# AUX_SteeringWheel_v4.net
KiCad netlist of a schematic drawn in Altium Designer
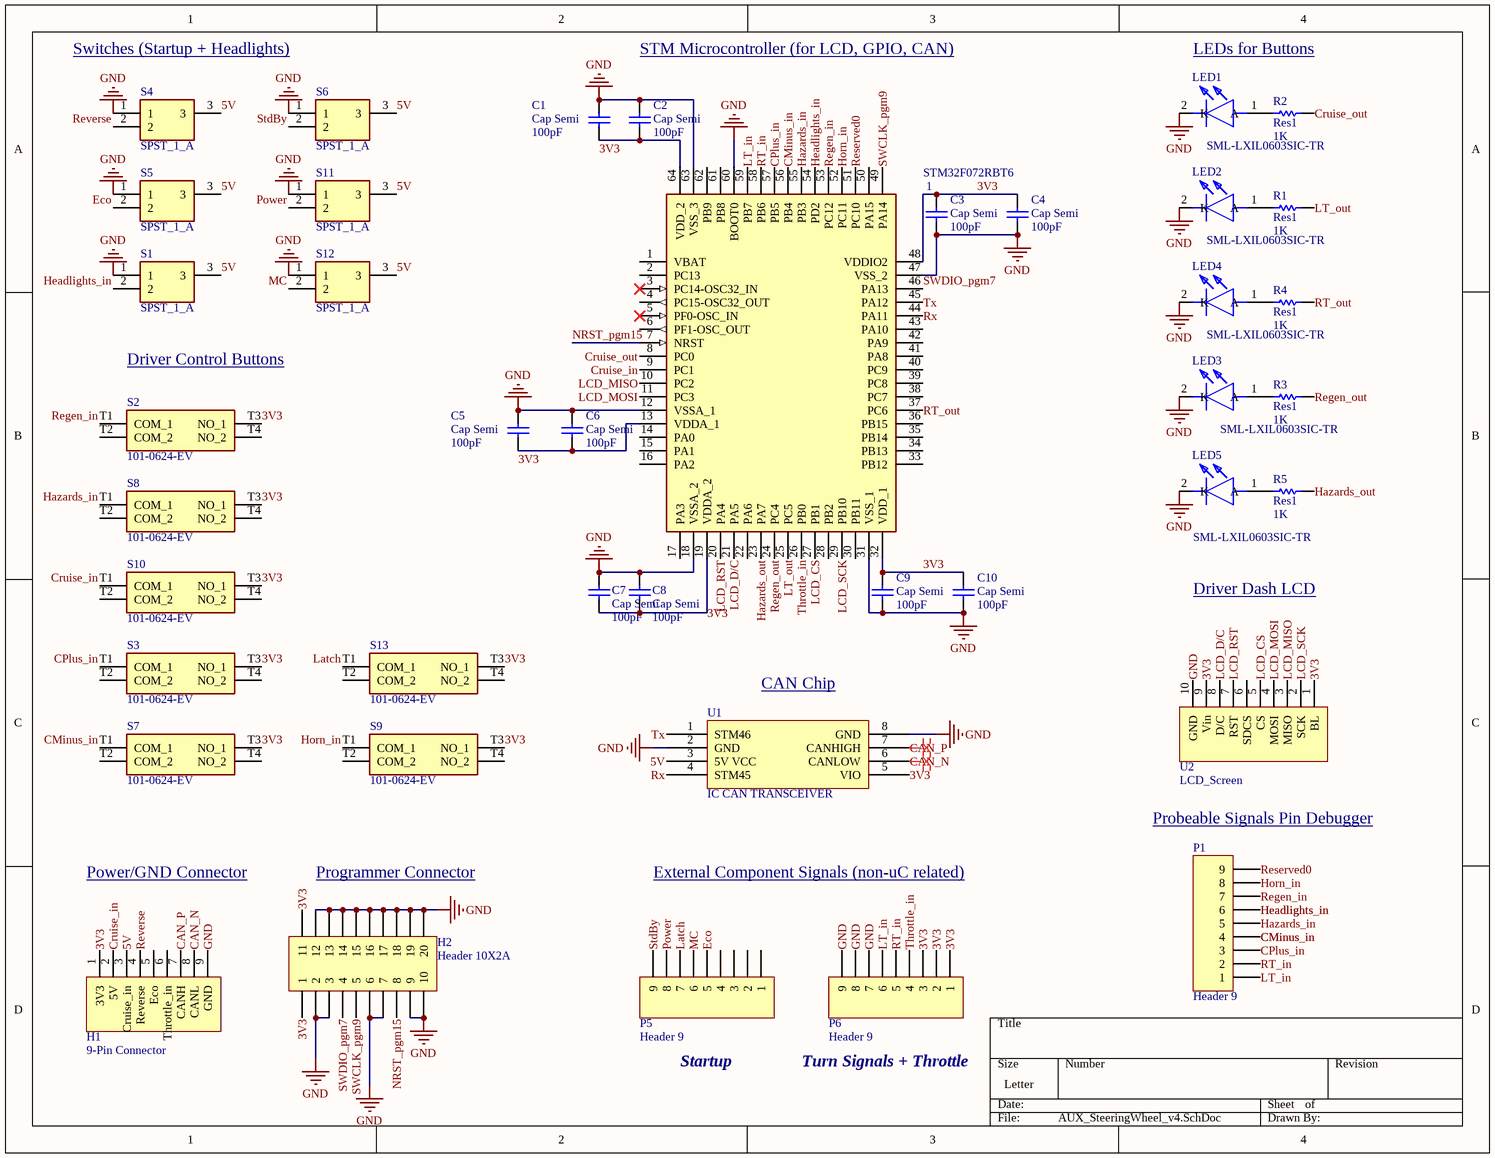
[diagram p0: AUX_SteeringWheel_v4.SchDoc]

(export (version "E")
  (design (tool "Eeschema 10.0.6"))
  (components
    (comp (ref "1")
      (value "STM32F072RBT6")
      (footprint "QFP50P1200X1200X160-64N")
      (description "Integrated Circuit")
      (fields (field (name "MOUSER PART NUMBER") "511-STM32F072RBT6"))
      (libsource (lib "AUX_SteeringWheel_v3") (part "STM32F072RBT6"))
    )
    (comp (ref "C1")
      (value "Cap Semi")
      (footprint "C1206")
      (description "Capacitor (Semiconductor SIM Model)")
      (fields (field (name "ALTIUM_VALUE") "100pF") (field (name "PUBLISHER") "Altium Limited"))
      (libsource (lib "Miscellaneous Devices") (part "Cap Semi"))
    )
    (comp (ref "C2")
      (value "Cap Semi")
      (footprint "C1206")
      (description "Capacitor (Semiconductor SIM Model)")
      (fields (field (name "ALTIUM_VALUE") "100pF") (field (name "PUBLISHER") "Altium Limited"))
      (libsource (lib "Miscellaneous Devices") (part "Cap Semi"))
    )
    (comp (ref "C3")
      (value "Cap Semi")
      (footprint "C1206")
      (description "Capacitor (Semiconductor SIM Model)")
      (fields (field (name "ALTIUM_VALUE") "100pF") (field (name "PUBLISHER") "Altium Limited"))
      (libsource (lib "Miscellaneous Devices") (part "Cap Semi"))
    )
    (comp (ref "C4")
      (value "Cap Semi")
      (footprint "C1206")
      (description "Capacitor (Semiconductor SIM Model)")
      (fields (field (name "ALTIUM_VALUE") "100pF") (field (name "PUBLISHER") "Altium Limited"))
      (libsource (lib "Miscellaneous Devices") (part "Cap Semi"))
    )
    (comp (ref "C5")
      (value "Cap Semi")
      (footprint "C1206")
      (description "Capacitor (Semiconductor SIM Model)")
      (fields (field (name "ALTIUM_VALUE") "100pF") (field (name "PUBLISHER") "Altium Limited"))
      (libsource (lib "Miscellaneous Devices") (part "Cap Semi"))
    )
    (comp (ref "C6")
      (value "Cap Semi")
      (footprint "C1206")
      (description "Capacitor (Semiconductor SIM Model)")
      (fields (field (name "ALTIUM_VALUE") "100pF") (field (name "PUBLISHER") "Altium Limited"))
      (libsource (lib "Miscellaneous Devices") (part "Cap Semi"))
    )
    (comp (ref "C7")
      (value "Cap Semi")
      (footprint "C1206")
      (description "Capacitor (Semiconductor SIM Model)")
      (fields (field (name "ALTIUM_VALUE") "100pF") (field (name "PUBLISHER") "Altium Limited"))
      (libsource (lib "Miscellaneous Devices") (part "Cap Semi"))
    )
    (comp (ref "C8")
      (value "Cap Semi")
      (footprint "C1206")
      (description "Capacitor (Semiconductor SIM Model)")
      (fields (field (name "ALTIUM_VALUE") "100pF") (field (name "PUBLISHER") "Altium Limited"))
      (libsource (lib "Miscellaneous Devices") (part "Cap Semi"))
    )
    (comp (ref "C9")
      (value "Cap Semi")
      (footprint "C1206")
      (description "Capacitor (Semiconductor SIM Model)")
      (fields (field (name "ALTIUM_VALUE") "100pF") (field (name "PUBLISHER") "Altium Limited"))
      (libsource (lib "Miscellaneous Devices") (part "Cap Semi"))
    )
    (comp (ref "C10")
      (value "Cap Semi")
      (footprint "C1206")
      (description "Capacitor (Semiconductor SIM Model)")
      (fields (field (name "ALTIUM_VALUE") "100pF") (field (name "PUBLISHER") "Altium Limited"))
      (libsource (lib "Miscellaneous Devices") (part "Cap Semi"))
    )
    (comp (ref "H1")
      (value "9-Pin Connector")
      (footprint "Rt_Angle_9-Pin")
      (libsource (lib "Aux_Lights_Daughter_library") (part "9-Pin Connector"))
    )
    (comp (ref "H2")
      (value "Header 10X2A")
      (footprint "HDR2X10_CEN")
      (description "Header, 10-Pin, Dual row")
      (fields (field (name "PUBLISHER") "Altium Limited"))
      (libsource (lib "Miscellaneous Connectors") (part "Header 10X2A"))
    )
    (comp (ref "LED1")
      (value "SML-LXIL0603SIC-TR")
      (footprint "LED thru hole")
      (description "Cruise")
      (fields (field (name "MOUSER2 PART NUMBER") "696-SMLLXIL0603SICTR"))
      (libsource (lib "*") (part "SML-LXIL0603SIC-TR"))
    )
    (comp (ref "LED2")
      (value "SML-LXIL0603SIC-TR")
      (footprint "LED thru hole")
      (description "Cruise")
      (fields (field (name "MOUSER2 PART NUMBER") "696-SMLLXIL0603SICTR"))
      (libsource (lib "*") (part "SML-LXIL0603SIC-TR"))
    )
    (comp (ref "LED3")
      (value "SML-LXIL0603SIC-TR")
      (footprint "LED thru hole")
      (description "Headlights")
      (fields (field (name "MOUSER2 PART NUMBER") "696-SMLLXIL0603SICTR"))
      (libsource (lib "*") (part "SML-LXIL0603SIC-TR"))
    )
    (comp (ref "LED4")
      (value "SML-LXIL0603SIC-TR")
      (footprint "LED thru hole")
      (description "Cruise")
      (fields (field (name "MOUSER2 PART NUMBER") "696-SMLLXIL0603SICTR"))
      (libsource (lib "*") (part "SML-LXIL0603SIC-TR"))
    )
    (comp (ref "LED5")
      (value "SML-LXIL0603SIC-TR")
      (footprint "LED thru hole")
      (description "Hazards")
      (fields (field (name "MOUSER2 PART NUMBER") "696-SMLLXIL0603SICTR"))
      (libsource (lib "*") (part "SML-LXIL0603SIC-TR"))
    )
    (comp (ref "P1")
      (value "Header 9")
      (footprint "HDR1X9")
      (description "Header, 9-Pin")
      (fields (field (name "PUBLISHER") "Altium Limited"))
      (libsource (lib "") (part "Header 9_1"))
    )
    (comp (ref "P5")
      (value "Header 9")
      (footprint "Rt_Angle_9-Pin")
      (description "Header, 9-Pin")
      (fields (field (name "PUBLISHER") "Altium Limited"))
      (libsource (lib "Miscellaneous Connectors") (part "Header 9"))
    )
    (comp (ref "P6")
      (value "Header 9")
      (footprint "Rt_Angle_9-Pin")
      (description "Header, 9-Pin")
      (fields (field (name "PUBLISHER") "Altium Limited"))
      (libsource (lib "Miscellaneous Connectors") (part "Header 9"))
    )
    (comp (ref "R1")
      (value "Res1")
      (footprint "AXIAL-0.3")
      (description "Resistor")
      (fields (field (name "ALTIUM_VALUE") "1K") (field (name "PUBLISHER") "Altium Limited"))
      (libsource (lib "Miscellaneous Devices") (part "Res1"))
    )
    (comp (ref "R2")
      (value "Res1")
      (footprint "AXIAL-0.3")
      (description "Resistor")
      (fields (field (name "ALTIUM_VALUE") "1K") (field (name "PUBLISHER") "Altium Limited"))
      (libsource (lib "Miscellaneous Devices") (part "Res1"))
    )
    (comp (ref "R3")
      (value "Res1")
      (footprint "AXIAL-0.3")
      (description "Resistor")
      (fields (field (name "ALTIUM_VALUE") "1K") (field (name "PUBLISHER") "Altium Limited"))
      (libsource (lib "Miscellaneous Devices") (part "Res1"))
    )
    (comp (ref "R4")
      (value "Res1")
      (footprint "AXIAL-0.3")
      (description "Resistor")
      (fields (field (name "ALTIUM_VALUE") "1K") (field (name "PUBLISHER") "Altium Limited"))
      (libsource (lib "Miscellaneous Devices") (part "Res1"))
    )
    (comp (ref "R5")
      (value "Res1")
      (footprint "AXIAL-0.3")
      (description "Resistor")
      (fields (field (name "ALTIUM_VALUE") "1K") (field (name "PUBLISHER") "Altium Limited"))
      (libsource (lib "Miscellaneous Devices") (part "Res1"))
    )
    (comp (ref "S1")
      (value "SPST_1_A")
      (footprint "2M1SP3T1B1M2QE")
      (description "Switch")
      (fields
        (field (name "MOUSER PART NUMBER") "691-2M1-SP1-T1B1M2QE")
        (field (name "MANUFACTURER_PART_NUMBER") "2M1-SP1-T1-B1-M2QE")
      )
      (libsource (lib "AUX_v7_3") (part "2M1-SP1-T1-B1-M2QE"))
    )
    (comp (ref "S2")
      (value "101-0624-EV")
      (footprint "1010624EV")
      (description "Switch")
      (libsource (lib "AUX_SteeringWheel_v3") (part "101-0624-EV"))
    )
    (comp (ref "S3")
      (value "101-0624-EV")
      (footprint "1010624EV")
      (description "Switch")
      (libsource (lib "AUX_SteeringWheel_v3") (part "101-0624-EV"))
    )
    (comp (ref "S4")
      (value "SPST_1_A")
      (footprint "2M1SP3T1B1M2QE")
      (description "Switch")
      (fields
        (field (name "MOUSER PART NUMBER") "691-2M1-SP1-T1B1M2QE")
        (field (name "MANUFACTURER_PART_NUMBER") "2M1-SP1-T1-B1-M2QE")
      )
      (libsource (lib "AUX_SteeringWheel_v3") (part "2M1-SP1-T1-B1-M2QE"))
    )
    (comp (ref "S5")
      (value "SPST_1_A")
      (footprint "2M1SP3T1B1M2QE")
      (description "Switch")
      (fields
        (field (name "MOUSER PART NUMBER") "691-2M1-SP1-T1B1M2QE")
        (field (name "MANUFACTURER_PART_NUMBER") "2M1-SP1-T1-B1-M2QE")
      )
      (libsource (lib "AUX_SteeringWheel_v3") (part "2M1-SP1-T1-B1-M2QE"))
    )
    (comp (ref "S6")
      (value "SPST_1_A")
      (footprint "2M1SP3T1B1M2QE")
      (description "Switch")
      (fields
        (field (name "MOUSER PART NUMBER") "691-2M1-SP1-T1B1M2QE")
        (field (name "MANUFACTURER_PART_NUMBER") "2M1-SP1-T1-B1-M2QE")
      )
      (libsource (lib "AUX_SteeringWheel_v3") (part "2M1-SP1-T1-B1-M2QE"))
    )
    (comp (ref "S7")
      (value "101-0624-EV")
      (footprint "1010624EV")
      (description "Switch")
      (libsource (lib "AUX_SteeringWheel_v3") (part "101-0624-EV"))
    )
    (comp (ref "S8")
      (value "101-0624-EV")
      (footprint "1010624EV")
      (description "Switch")
      (libsource (lib "AUX_SteeringWheel_v3") (part "101-0624-EV"))
    )
    (comp (ref "S9")
      (value "101-0624-EV")
      (footprint "1010624EV")
      (description "Switch")
      (libsource (lib "AUX_SteeringWheel_v3") (part "101-0624-EV"))
    )
    (comp (ref "S10")
      (value "101-0624-EV")
      (footprint "1010624EV")
      (description "Switch")
      (libsource (lib "AUX_SteeringWheel_v3") (part "101-0624-EV"))
    )
    (comp (ref "S11")
      (value "SPST_1_A")
      (footprint "2M1SP3T1B1M2QE")
      (description "Switch")
      (fields
        (field (name "MOUSER PART NUMBER") "691-2M1-SP1-T1B1M2QE")
        (field (name "MANUFACTURER_PART_NUMBER") "2M1-SP1-T1-B1-M2QE")
      )
      (libsource (lib "AUX_SteeringWheel_v3") (part "2M1-SP1-T1-B1-M2QE"))
    )
    (comp (ref "S12")
      (value "SPST_1_A")
      (footprint "2M1SP3T1B1M2QE")
      (description "Switch")
      (fields
        (field (name "MOUSER PART NUMBER") "691-2M1-SP1-T1B1M2QE")
        (field (name "MANUFACTURER_PART_NUMBER") "2M1-SP1-T1-B1-M2QE")
      )
      (libsource (lib "AUX_SteeringWheel_v3") (part "2M1-SP1-T1-B1-M2QE"))
    )
    (comp (ref "S13")
      (value "101-0624-EV")
      (footprint "1010624EV")
      (description "Switch")
      (libsource (lib "AUX_SteeringWheel_v3") (part "101-0624-EV"))
    )
    (comp (ref "U1")
      (value "IC CAN TRANSCEIVER")
      (footprint "CAN TRANSCEIVER")
      (libsource (lib "Components") (part "CAN TRANSCEIVER"))
    )
    (comp (ref "U2")
      (value "LCD_Screen")
      (footprint "LCD_Screen")
      (description "LCD Display Screen")
      (libsource (lib "Aux_Lights_Daughter_library") (part "LCD_Screen"))
    )
  )
  (nets
    (net (code "1") (name "/3V3") (class "Default")
      (node (ref "1") (pin "13") (pinfunction "VDDA_1_13") (pintype "power_in"))
      (node (ref "1") (pin "19") (pinfunction "VDDA_2_19") (pintype "power_in"))
      (node (ref "1") (pin "32") (pinfunction "VDD_1_32") (pintype "power_in"))
      (node (ref "1") (pin "48") (pinfunction "VDDIO2_48") (pintype "power_in"))
      (node (ref "1") (pin "64") (pinfunction "VDD_2_64") (pintype "power_in"))
      (node (ref "C1") (pin "1") (pinfunction "1_1") (pintype "passive"))
      (node (ref "C10") (pin "2") (pinfunction "2_2") (pintype "passive"))
      (node (ref "C2") (pin "1") (pinfunction "1_1") (pintype "passive"))
      (node (ref "C3") (pin "2") (pinfunction "2_2") (pintype "passive"))
      (node (ref "C4") (pin "2") (pinfunction "2_2") (pintype "passive"))
      (node (ref "C5") (pin "1") (pinfunction "1_1") (pintype "passive"))
      (node (ref "C6") (pin "1") (pinfunction "1_1") (pintype "passive"))
      (node (ref "C7") (pin "1") (pinfunction "1_1") (pintype "passive"))
      (node (ref "C8") (pin "1") (pinfunction "1_1") (pintype "passive"))
      (node (ref "C9") (pin "2") (pinfunction "2_2") (pintype "passive"))
      (node (ref "H1") (pin "1") (pinfunction "3V3_1") (pintype "passive"))
      (node (ref "H2") (pin "1") (pinfunction "1_1") (pintype "passive"))
      (node (ref "H2") (pin "11") (pinfunction "11_11") (pintype "passive"))
      (node (ref "P6") (pin "1") (pinfunction "1_1") (pintype "passive"))
      (node (ref "P6") (pin "2") (pinfunction "2_2") (pintype "passive"))
      (node (ref "P6") (pin "3") (pinfunction "3_3") (pintype "passive"))
      (node (ref "S10") (pin "T3") (pinfunction "NO_1_T3") (pintype "passive"))
      (node (ref "S13") (pin "T3") (pinfunction "NO_1_T3") (pintype "passive"))
      (node (ref "S2") (pin "T3") (pinfunction "NO_1_T3") (pintype "passive"))
      (node (ref "S3") (pin "T3") (pinfunction "NO_1_T3") (pintype "passive"))
      (node (ref "S7") (pin "T3") (pinfunction "NO_1_T3") (pintype "passive"))
      (node (ref "S8") (pin "T3") (pinfunction "NO_1_T3") (pintype "passive"))
      (node (ref "S9") (pin "T3") (pinfunction "NO_1_T3") (pintype "passive"))
      (node (ref "U1") (pin "5") (pinfunction "VIO_5") (pintype "passive"))
      (node (ref "U2") (pin "1") (pinfunction "BL_1") (pintype "passive"))
      (node (ref "U2") (pin "9") (pinfunction "Vin_9") (pintype "passive"))
    )
    (net (code "2") (name "/5V") (class "Default")
      (node (ref "H1") (pin "3") (pinfunction "Cruise_in_3") (pintype "passive"))
      (node (ref "S1") (pin "3") (pinfunction "3_3") (pintype "passive"))
      (node (ref "S11") (pin "3") (pinfunction "3_3") (pintype "passive"))
      (node (ref "S12") (pin "3") (pinfunction "3_3") (pintype "passive"))
      (node (ref "S4") (pin "3") (pinfunction "3_3") (pintype "passive"))
      (node (ref "S5") (pin "3") (pinfunction "3_3") (pintype "passive"))
      (node (ref "S6") (pin "3") (pinfunction "3_3") (pintype "passive"))
      (node (ref "U1") (pin "3") (pinfunction "5V_VCC_3") (pintype "passive"))
    )
    (net (code "3") (name "/CAN_N") (class "Default")
      (node (ref "H1") (pin "8") (pinfunction "CANL_8") (pintype "passive"))
      (node (ref "U1") (pin "6") (pinfunction "CANLOW_6") (pintype "passive"))
    )
    (net (code "4") (name "/CAN_P") (class "Default")
      (node (ref "H1") (pin "7") (pinfunction "CANH_7") (pintype "passive"))
      (node (ref "U1") (pin "7") (pinfunction "CANHIGH_7") (pintype "passive"))
    )
    (net (code "5") (name "/CMinus_in") (class "Default")
      (node (ref "1") (pin "56") (pinfunction "PB4_56") (pintype "passive"))
      (node (ref "P1") (pin "4") (pinfunction "4_4") (pintype "passive"))
      (node (ref "S7") (pin "T1") (pinfunction "COM_1_T1") (pintype "passive"))
    )
    (net (code "6") (name "/CPlus_in") (class "Default")
      (node (ref "1") (pin "57") (pinfunction "PB5_57") (pintype "passive"))
      (node (ref "P1") (pin "3") (pinfunction "3_3") (pintype "passive"))
      (node (ref "S3") (pin "T1") (pinfunction "COM_1_T1") (pintype "passive"))
    )
    (net (code "7") (name "/Cruise_in") (class "Default")
      (node (ref "1") (pin "9") (pinfunction "PC1_9") (pintype "passive"))
      (node (ref "H1") (pin "2") (pinfunction "5V_2") (pintype "passive"))
      (node (ref "S10") (pin "T1") (pinfunction "COM_1_T1") (pintype "passive"))
    )
    (net (code "8") (name "/Cruise_out") (class "Default")
      (node (ref "1") (pin "8") (pinfunction "PC0_8") (pintype "passive"))
      (node (ref "R2") (pin "1") (pinfunction "1_1") (pintype "passive"))
    )
    (net (code "9") (name "/Eco") (class "Default")
      (node (ref "P5") (pin "5") (pinfunction "5_5") (pintype "passive"))
      (node (ref "S5") (pin "2") (pinfunction "2_2") (pintype "passive"))
    )
    (net (code "10") (name "/Hazards_in") (class "Default")
      (node (ref "1") (pin "55") (pinfunction "PB3_55") (pintype "passive"))
      (node (ref "P1") (pin "5") (pinfunction "5_5") (pintype "passive"))
      (node (ref "S8") (pin "T1") (pinfunction "COM_1_T1") (pintype "passive"))
    )
    (net (code "11") (name "/Hazards_out") (class "Default")
      (node (ref "1") (pin "23") (pinfunction "PA7_23") (pintype "passive"))
      (node (ref "R5") (pin "1") (pinfunction "1_1") (pintype "passive"))
    )
    (net (code "12") (name "/Headlights_in") (class "Default")
      (node (ref "1") (pin "54") (pinfunction "PD2_54") (pintype "passive"))
      (node (ref "P1") (pin "6") (pinfunction "6_6") (pintype "passive"))
      (node (ref "S1") (pin "2") (pinfunction "2_2") (pintype "passive"))
    )
    (net (code "13") (name "/Horn_in") (class "Default")
      (node (ref "1") (pin "52") (pinfunction "PC11_52") (pintype "passive"))
      (node (ref "P1") (pin "8") (pinfunction "8_8") (pintype "passive"))
      (node (ref "S9") (pin "T1") (pinfunction "COM_1_T1") (pintype "passive"))
    )
    (net (code "14") (name "/LCD_CS") (class "Default")
      (node (ref "1") (pin "27") (pinfunction "PB1_27") (pintype "passive"))
      (node (ref "U2") (pin "5") (pinfunction "CS_5") (pintype "passive"))
    )
    (net (code "15") (name "/LCD_D{slash}C") (class "Default")
      (node (ref "1") (pin "21") (pinfunction "PA5_21") (pintype "passive"))
      (node (ref "U2") (pin "8") (pinfunction "D/C_8") (pintype "passive"))
    )
    (net (code "16") (name "/LCD_MISO") (class "Default")
      (node (ref "1") (pin "10") (pinfunction "PC2_10") (pintype "passive"))
      (node (ref "U2") (pin "3") (pinfunction "MISO_3") (pintype "passive"))
    )
    (net (code "17") (name "/LCD_MOSI") (class "Default")
      (node (ref "1") (pin "11") (pinfunction "PC3_11") (pintype "passive"))
      (node (ref "U2") (pin "4") (pinfunction "MOSI_4") (pintype "passive"))
    )
    (net (code "18") (name "/LCD_RST") (class "Default")
      (node (ref "1") (pin "20") (pinfunction "PA4_20") (pintype "passive"))
      (node (ref "U2") (pin "7") (pinfunction "RST_7") (pintype "passive"))
    )
    (net (code "19") (name "/LCD_SCK") (class "Default")
      (node (ref "1") (pin "29") (pinfunction "PB10_29") (pintype "passive"))
      (node (ref "U2") (pin "2") (pinfunction "SCK_2") (pintype "passive"))
    )
    (net (code "20") (name "/LT_in") (class "Default")
      (node (ref "1") (pin "59") (pinfunction "PB7_59") (pintype "passive"))
      (node (ref "P1") (pin "1") (pinfunction "1_1") (pintype "passive"))
      (node (ref "P6") (pin "6") (pinfunction "6_6") (pintype "passive"))
    )
    (net (code "21") (name "/LT_out") (class "Default")
      (node (ref "1") (pin "25") (pinfunction "PC5_25") (pintype "passive"))
      (node (ref "R1") (pin "1") (pinfunction "1_1") (pintype "passive"))
    )
    (net (code "22") (name "/Latch") (class "Default")
      (node (ref "P5") (pin "7") (pinfunction "7_7") (pintype "passive"))
      (node (ref "S13") (pin "T1") (pinfunction "COM_1_T1") (pintype "passive"))
    )
    (net (code "23") (name "/MC") (class "Default")
      (node (ref "P5") (pin "6") (pinfunction "6_6") (pintype "passive"))
      (node (ref "S12") (pin "2") (pinfunction "2_2") (pintype "passive"))
    )
    (net (code "24") (name "/NRST_pgm15") (class "Default")
      (node (ref "1") (pin "7") (pinfunction "NRST_7") (pintype "input"))
      (node (ref "H2") (pin "8") (pinfunction "8_8") (pintype "passive"))
    )
    (net (code "25") (name "/Power") (class "Default")
      (node (ref "P5") (pin "8") (pinfunction "8_8") (pintype "passive"))
      (node (ref "S11") (pin "2") (pinfunction "2_2") (pintype "passive"))
    )
    (net (code "26") (name "/RT_in") (class "Default")
      (node (ref "1") (pin "58") (pinfunction "PB6_58") (pintype "passive"))
      (node (ref "P1") (pin "2") (pinfunction "2_2") (pintype "passive"))
      (node (ref "P6") (pin "5") (pinfunction "5_5") (pintype "passive"))
    )
    (net (code "27") (name "/RT_out") (class "Default")
      (node (ref "1") (pin "37") (pinfunction "PC6_37") (pintype "passive"))
      (node (ref "R4") (pin "1") (pinfunction "1_1") (pintype "passive"))
    )
    (net (code "28") (name "/Regen_in") (class "Default")
      (node (ref "1") (pin "53") (pinfunction "PC12_53") (pintype "passive"))
      (node (ref "P1") (pin "7") (pinfunction "7_7") (pintype "passive"))
      (node (ref "S2") (pin "T1") (pinfunction "COM_1_T1") (pintype "passive"))
    )
    (net (code "29") (name "/Regen_out") (class "Default")
      (node (ref "1") (pin "24") (pinfunction "PC4_24") (pintype "passive"))
      (node (ref "R3") (pin "1") (pinfunction "1_1") (pintype "passive"))
    )
    (net (code "30") (name "/Reserved0") (class "Default")
      (node (ref "1") (pin "51") (pinfunction "PC10_51") (pintype "passive"))
      (node (ref "P1") (pin "9") (pinfunction "9_9") (pintype "passive"))
    )
    (net (code "31") (name "/Reverse") (class "Default")
      (node (ref "H1") (pin "4") (pinfunction "Reverse_4") (pintype "passive"))
      (node (ref "S4") (pin "2") (pinfunction "2_2") (pintype "passive"))
    )
    (net (code "32") (name "/Rx") (class "Default")
      (node (ref "1") (pin "44") (pinfunction "PA11_44") (pintype "passive"))
      (node (ref "U1") (pin "4") (pinfunction "STM45_4") (pintype "passive"))
    )
    (net (code "33") (name "/SWCLK_pgm9") (class "Default")
      (node (ref "1") (pin "49") (pinfunction "PA14_49") (pintype "passive"))
      (node (ref "H2") (pin "5") (pinfunction "5_5") (pintype "passive"))
    )
    (net (code "34") (name "/SWDIO_pgm7") (class "Default")
      (node (ref "1") (pin "46") (pinfunction "PA13_46") (pintype "passive"))
      (node (ref "H2") (pin "4") (pinfunction "4_4") (pintype "passive"))
    )
    (net (code "35") (name "/StdBy") (class "Default")
      (node (ref "P5") (pin "9") (pinfunction "9_9") (pintype "passive"))
      (node (ref "S6") (pin "2") (pinfunction "2_2") (pintype "passive"))
    )
    (net (code "36") (name "/Throttle_in") (class "Default")
      (node (ref "1") (pin "26") (pinfunction "PB0_26") (pintype "passive"))
      (node (ref "P6") (pin "4") (pinfunction "4_4") (pintype "passive"))
    )
    (net (code "37") (name "/Tx") (class "Default")
      (node (ref "1") (pin "45") (pinfunction "PA12_45") (pintype "passive"))
      (node (ref "U1") (pin "1") (pinfunction "STM46_1") (pintype "passive"))
    )
    (net (code "38") (name "GND") (class "Default")
      (node (ref "1") (pin "12") (pinfunction "VSSA_1_12") (pintype "power_in"))
      (node (ref "1") (pin "18") (pinfunction "VSSA_2_18") (pintype "power_in"))
      (node (ref "1") (pin "31") (pinfunction "VSS_1_31") (pintype "power_in"))
      (node (ref "1") (pin "47") (pinfunction "VSS_2_47") (pintype "power_in"))
      (node (ref "1") (pin "60") (pinfunction "BOOT0_60") (pintype "passive"))
      (node (ref "1") (pin "63") (pinfunction "VSS_3_63") (pintype "power_in"))
      (node (ref "C1") (pin "2") (pinfunction "2_2") (pintype "passive"))
      (node (ref "C10") (pin "1") (pinfunction "1_1") (pintype "passive"))
      (node (ref "C2") (pin "2") (pinfunction "2_2") (pintype "passive"))
      (node (ref "C3") (pin "1") (pinfunction "1_1") (pintype "passive"))
      (node (ref "C4") (pin "1") (pinfunction "1_1") (pintype "passive"))
      (node (ref "C5") (pin "2") (pinfunction "2_2") (pintype "passive"))
      (node (ref "C6") (pin "2") (pinfunction "2_2") (pintype "passive"))
      (node (ref "C7") (pin "2") (pinfunction "2_2") (pintype "passive"))
      (node (ref "C8") (pin "2") (pinfunction "2_2") (pintype "passive"))
      (node (ref "C9") (pin "1") (pinfunction "1_1") (pintype "passive"))
      (node (ref "H1") (pin "9") (pinfunction "GND_9") (pintype "passive"))
      (node (ref "H2") (pin "10") (pinfunction "10_10") (pintype "passive"))
      (node (ref "H2") (pin "12") (pinfunction "12_12") (pintype "passive"))
      (node (ref "H2") (pin "13") (pinfunction "13_13") (pintype "passive"))
      (node (ref "H2") (pin "14") (pinfunction "14_14") (pintype "passive"))
      (node (ref "H2") (pin "15") (pinfunction "15_15") (pintype "passive"))
      (node (ref "H2") (pin "16") (pinfunction "16_16") (pintype "passive"))
      (node (ref "H2") (pin "17") (pinfunction "17_17") (pintype "passive"))
      (node (ref "H2") (pin "18") (pinfunction "18_18") (pintype "passive"))
      (node (ref "H2") (pin "19") (pinfunction "19_19") (pintype "passive"))
      (node (ref "H2") (pin "2") (pinfunction "2_2") (pintype "passive"))
      (node (ref "H2") (pin "20") (pinfunction "20_20") (pintype "passive"))
      (node (ref "H2") (pin "3") (pinfunction "3_3") (pintype "passive"))
      (node (ref "H2") (pin "6") (pinfunction "6_6") (pintype "passive"))
      (node (ref "H2") (pin "7") (pinfunction "7_7") (pintype "passive"))
      (node (ref "H2") (pin "9") (pinfunction "9_9") (pintype "passive"))
      (node (ref "LED1") (pin "2") (pinfunction "K_2") (pintype "passive"))
      (node (ref "LED2") (pin "2") (pinfunction "K_2") (pintype "passive"))
      (node (ref "LED3") (pin "2") (pinfunction "K_2") (pintype "passive"))
      (node (ref "LED4") (pin "2") (pinfunction "K_2") (pintype "passive"))
      (node (ref "LED5") (pin "2") (pinfunction "K_2") (pintype "passive"))
      (node (ref "P6") (pin "7") (pinfunction "7_7") (pintype "passive"))
      (node (ref "P6") (pin "8") (pinfunction "8_8") (pintype "passive"))
      (node (ref "P6") (pin "9") (pinfunction "9_9") (pintype "passive"))
      (node (ref "S1") (pin "1") (pinfunction "1_1") (pintype "passive"))
      (node (ref "S11") (pin "1") (pinfunction "1_1") (pintype "passive"))
      (node (ref "S12") (pin "1") (pinfunction "1_1") (pintype "passive"))
      (node (ref "S4") (pin "1") (pinfunction "1_1") (pintype "passive"))
      (node (ref "S5") (pin "1") (pinfunction "1_1") (pintype "passive"))
      (node (ref "S6") (pin "1") (pinfunction "1_1") (pintype "passive"))
      (node (ref "U1") (pin "2") (pinfunction "GND_2") (pintype "passive"))
      (node (ref "U1") (pin "8") (pinfunction "GND_8") (pintype "passive"))
      (node (ref "U2") (pin "10") (pinfunction "GND_10") (pintype "passive"))
    )
    (net (code "39") (name "Net-(LED1-A)") (class "Default")
      (node (ref "LED1") (pin "1") (pinfunction "A_1") (pintype "passive"))
      (node (ref "R2") (pin "2") (pinfunction "2_2") (pintype "passive"))
    )
    (net (code "40") (name "Net-(LED2-A)") (class "Default")
      (node (ref "LED2") (pin "1") (pinfunction "A_1") (pintype "passive"))
      (node (ref "R1") (pin "2") (pinfunction "2_2") (pintype "passive"))
    )
    (net (code "41") (name "Net-(LED3-A)") (class "Default")
      (node (ref "LED3") (pin "1") (pinfunction "A_1") (pintype "passive"))
      (node (ref "R3") (pin "2") (pinfunction "2_2") (pintype "passive"))
    )
    (net (code "42") (name "Net-(LED4-A)") (class "Default")
      (node (ref "LED4") (pin "1") (pinfunction "A_1") (pintype "passive"))
      (node (ref "R4") (pin "2") (pinfunction "2_2") (pintype "passive"))
    )
    (net (code "43") (name "Net-(LED5-A)") (class "Default")
      (node (ref "LED5") (pin "1") (pinfunction "A_1") (pintype "passive"))
      (node (ref "R5") (pin "2") (pinfunction "2_2") (pintype "passive"))
    )
    (net (code "44") (name "unconnected-(1-PA0-Pad14)") (class "Default")
      (node (ref "1") (pin "14") (pinfunction "PA0_14") (pintype "passive"))
    )
    (net (code "45") (name "unconnected-(1-PA1-Pad15)") (class "Default")
      (node (ref "1") (pin "15") (pinfunction "PA1_15") (pintype "passive"))
    )
    (net (code "46") (name "unconnected-(1-PA2-Pad16)") (class "Default")
      (node (ref "1") (pin "16") (pinfunction "PA2_16") (pintype "passive"))
    )
    (net (code "47") (name "unconnected-(1-PA3-Pad17)") (class "Default")
      (node (ref "1") (pin "17") (pinfunction "PA3_17") (pintype "passive"))
    )
    (net (code "48") (name "unconnected-(1-PA6-Pad22)") (class "Default")
      (node (ref "1") (pin "22") (pinfunction "PA6_22") (pintype "passive"))
    )
    (net (code "49") (name "unconnected-(1-PA8-Pad41)") (class "Default")
      (node (ref "1") (pin "41") (pinfunction "PA8_41") (pintype "passive"))
    )
    (net (code "50") (name "unconnected-(1-PA9-Pad42)") (class "Default")
      (node (ref "1") (pin "42") (pinfunction "PA9_42") (pintype "passive"))
    )
    (net (code "51") (name "unconnected-(1-PA10-Pad43)") (class "Default")
      (node (ref "1") (pin "43") (pinfunction "PA10_43") (pintype "passive"))
    )
    (net (code "52") (name "unconnected-(1-PA15-Pad50)") (class "Default")
      (node (ref "1") (pin "50") (pinfunction "PA15_50") (pintype "passive"))
    )
    (net (code "53") (name "unconnected-(1-PB2-Pad28)") (class "Default")
      (node (ref "1") (pin "28") (pinfunction "PB2_28") (pintype "passive"))
    )
    (net (code "54") (name "unconnected-(1-PB8-Pad61)") (class "Default")
      (node (ref "1") (pin "61") (pinfunction "PB8_61") (pintype "passive"))
    )
    (net (code "55") (name "unconnected-(1-PB9-Pad62)") (class "Default")
      (node (ref "1") (pin "62") (pinfunction "PB9_62") (pintype "passive"))
    )
    (net (code "56") (name "unconnected-(1-PB11-Pad30)") (class "Default")
      (node (ref "1") (pin "30") (pinfunction "PB11_30") (pintype "passive"))
    )
    (net (code "57") (name "unconnected-(1-PB12-Pad33)") (class "Default")
      (node (ref "1") (pin "33") (pinfunction "PB12_33") (pintype "passive"))
    )
    (net (code "58") (name "unconnected-(1-PB13-Pad34)") (class "Default")
      (node (ref "1") (pin "34") (pinfunction "PB13_34") (pintype "passive"))
    )
    (net (code "59") (name "unconnected-(1-PB14-Pad35)") (class "Default")
      (node (ref "1") (pin "35") (pinfunction "PB14_35") (pintype "passive"))
    )
    (net (code "60") (name "unconnected-(1-PB15-Pad36)") (class "Default")
      (node (ref "1") (pin "36") (pinfunction "PB15_36") (pintype "passive"))
    )
    (net (code "61") (name "unconnected-(1-PC7-Pad38)") (class "Default")
      (node (ref "1") (pin "38") (pinfunction "PC7_38") (pintype "passive"))
    )
    (net (code "62") (name "unconnected-(1-PC8-Pad39)") (class "Default")
      (node (ref "1") (pin "39") (pinfunction "PC8_39") (pintype "passive"))
    )
    (net (code "63") (name "unconnected-(1-PC9-Pad40)") (class "Default")
      (node (ref "1") (pin "40") (pinfunction "PC9_40") (pintype "passive"))
    )
    (net (code "64") (name "unconnected-(1-PC13-Pad2)") (class "Default")
      (node (ref "1") (pin "2") (pinfunction "PC13_2") (pintype "passive"))
    )
    (net (code "65") (name "unconnected-(1-PC14-OSC32_IN-Pad3)") (class "Default")
      (node (ref "1") (pin "3") (pinfunction "PC14-OSC32_IN_3") (pintype "input+no_connect"))
    )
    (net (code "66") (name "unconnected-(1-PC15-OSC32_OUT-Pad4)") (class "Default")
      (node (ref "1") (pin "4") (pinfunction "PC15-OSC32_OUT_4") (pintype "output"))
    )
    (net (code "67") (name "unconnected-(1-PF0-OSC_IN-Pad5)") (class "Default")
      (node (ref "1") (pin "5") (pinfunction "PF0-OSC_IN_5") (pintype "input+no_connect"))
    )
    (net (code "68") (name "unconnected-(1-PF1-OSC_OUT-Pad6)") (class "Default")
      (node (ref "1") (pin "6") (pinfunction "PF1-OSC_OUT_6") (pintype "output"))
    )
    (net (code "69") (name "unconnected-(1-VBAT-Pad1)") (class "Default")
      (node (ref "1") (pin "1") (pinfunction "VBAT_1") (pintype "passive"))
    )
    (net (code "70") (name "unconnected-(H1-Eco-Pad5)") (class "Default")
      (node (ref "H1") (pin "5") (pinfunction "Eco_5") (pintype "passive"))
    )
    (net (code "71") (name "unconnected-(H1-Throttle_in-Pad6)") (class "Default")
      (node (ref "H1") (pin "6") (pinfunction "Throttle_in_6") (pintype "passive"))
    )
    (net (code "72") (name "unconnected-(P5-Pad1)") (class "Default")
      (node (ref "P5") (pin "1") (pinfunction "1_1") (pintype "passive"))
    )
    (net (code "73") (name "unconnected-(P5-Pad2)") (class "Default")
      (node (ref "P5") (pin "2") (pinfunction "2_2") (pintype "passive"))
    )
    (net (code "74") (name "unconnected-(P5-Pad3)") (class "Default")
      (node (ref "P5") (pin "3") (pinfunction "3_3") (pintype "passive"))
    )
    (net (code "75") (name "unconnected-(P5-Pad4)") (class "Default")
      (node (ref "P5") (pin "4") (pinfunction "4_4") (pintype "passive"))
    )
    (net (code "76") (name "unconnected-(S2-COM_2-PadT2)") (class "Default")
      (node (ref "S2") (pin "T2") (pinfunction "COM_2_T2") (pintype "passive"))
    )
    (net (code "77") (name "unconnected-(S2-NO_2-PadT4)") (class "Default")
      (node (ref "S2") (pin "T4") (pinfunction "NO_2_T4") (pintype "passive"))
    )
    (net (code "78") (name "unconnected-(S3-COM_2-PadT2)") (class "Default")
      (node (ref "S3") (pin "T2") (pinfunction "COM_2_T2") (pintype "passive"))
    )
    (net (code "79") (name "unconnected-(S3-NO_2-PadT4)") (class "Default")
      (node (ref "S3") (pin "T4") (pinfunction "NO_2_T4") (pintype "passive"))
    )
    (net (code "80") (name "unconnected-(S7-COM_2-PadT2)") (class "Default")
      (node (ref "S7") (pin "T2") (pinfunction "COM_2_T2") (pintype "passive"))
    )
    (net (code "81") (name "unconnected-(S7-NO_2-PadT4)") (class "Default")
      (node (ref "S7") (pin "T4") (pinfunction "NO_2_T4") (pintype "passive"))
    )
    (net (code "82") (name "unconnected-(S8-COM_2-PadT2)") (class "Default")
      (node (ref "S8") (pin "T2") (pinfunction "COM_2_T2") (pintype "passive"))
    )
    (net (code "83") (name "unconnected-(S8-NO_2-PadT4)") (class "Default")
      (node (ref "S8") (pin "T4") (pinfunction "NO_2_T4") (pintype "passive"))
    )
    (net (code "84") (name "unconnected-(S9-COM_2-PadT2)") (class "Default")
      (node (ref "S9") (pin "T2") (pinfunction "COM_2_T2") (pintype "passive"))
    )
    (net (code "85") (name "unconnected-(S9-NO_2-PadT4)") (class "Default")
      (node (ref "S9") (pin "T4") (pinfunction "NO_2_T4") (pintype "passive"))
    )
    (net (code "86") (name "unconnected-(S10-COM_2-PadT2)") (class "Default")
      (node (ref "S10") (pin "T2") (pinfunction "COM_2_T2") (pintype "passive"))
    )
    (net (code "87") (name "unconnected-(S10-NO_2-PadT4)") (class "Default")
      (node (ref "S10") (pin "T4") (pinfunction "NO_2_T4") (pintype "passive"))
    )
    (net (code "88") (name "unconnected-(S13-COM_2-PadT2)") (class "Default")
      (node (ref "S13") (pin "T2") (pinfunction "COM_2_T2") (pintype "passive"))
    )
    (net (code "89") (name "unconnected-(S13-NO_2-PadT4)") (class "Default")
      (node (ref "S13") (pin "T4") (pinfunction "NO_2_T4") (pintype "passive"))
    )
    (net (code "90") (name "unconnected-(U2-SDCS-Pad6)") (class "Default")
      (node (ref "U2") (pin "6") (pinfunction "SDCS_6") (pintype "passive"))
    )
  )
)
